# USBdrive_charging.net
KiCad netlist of a schematic drawn in Altium Designer
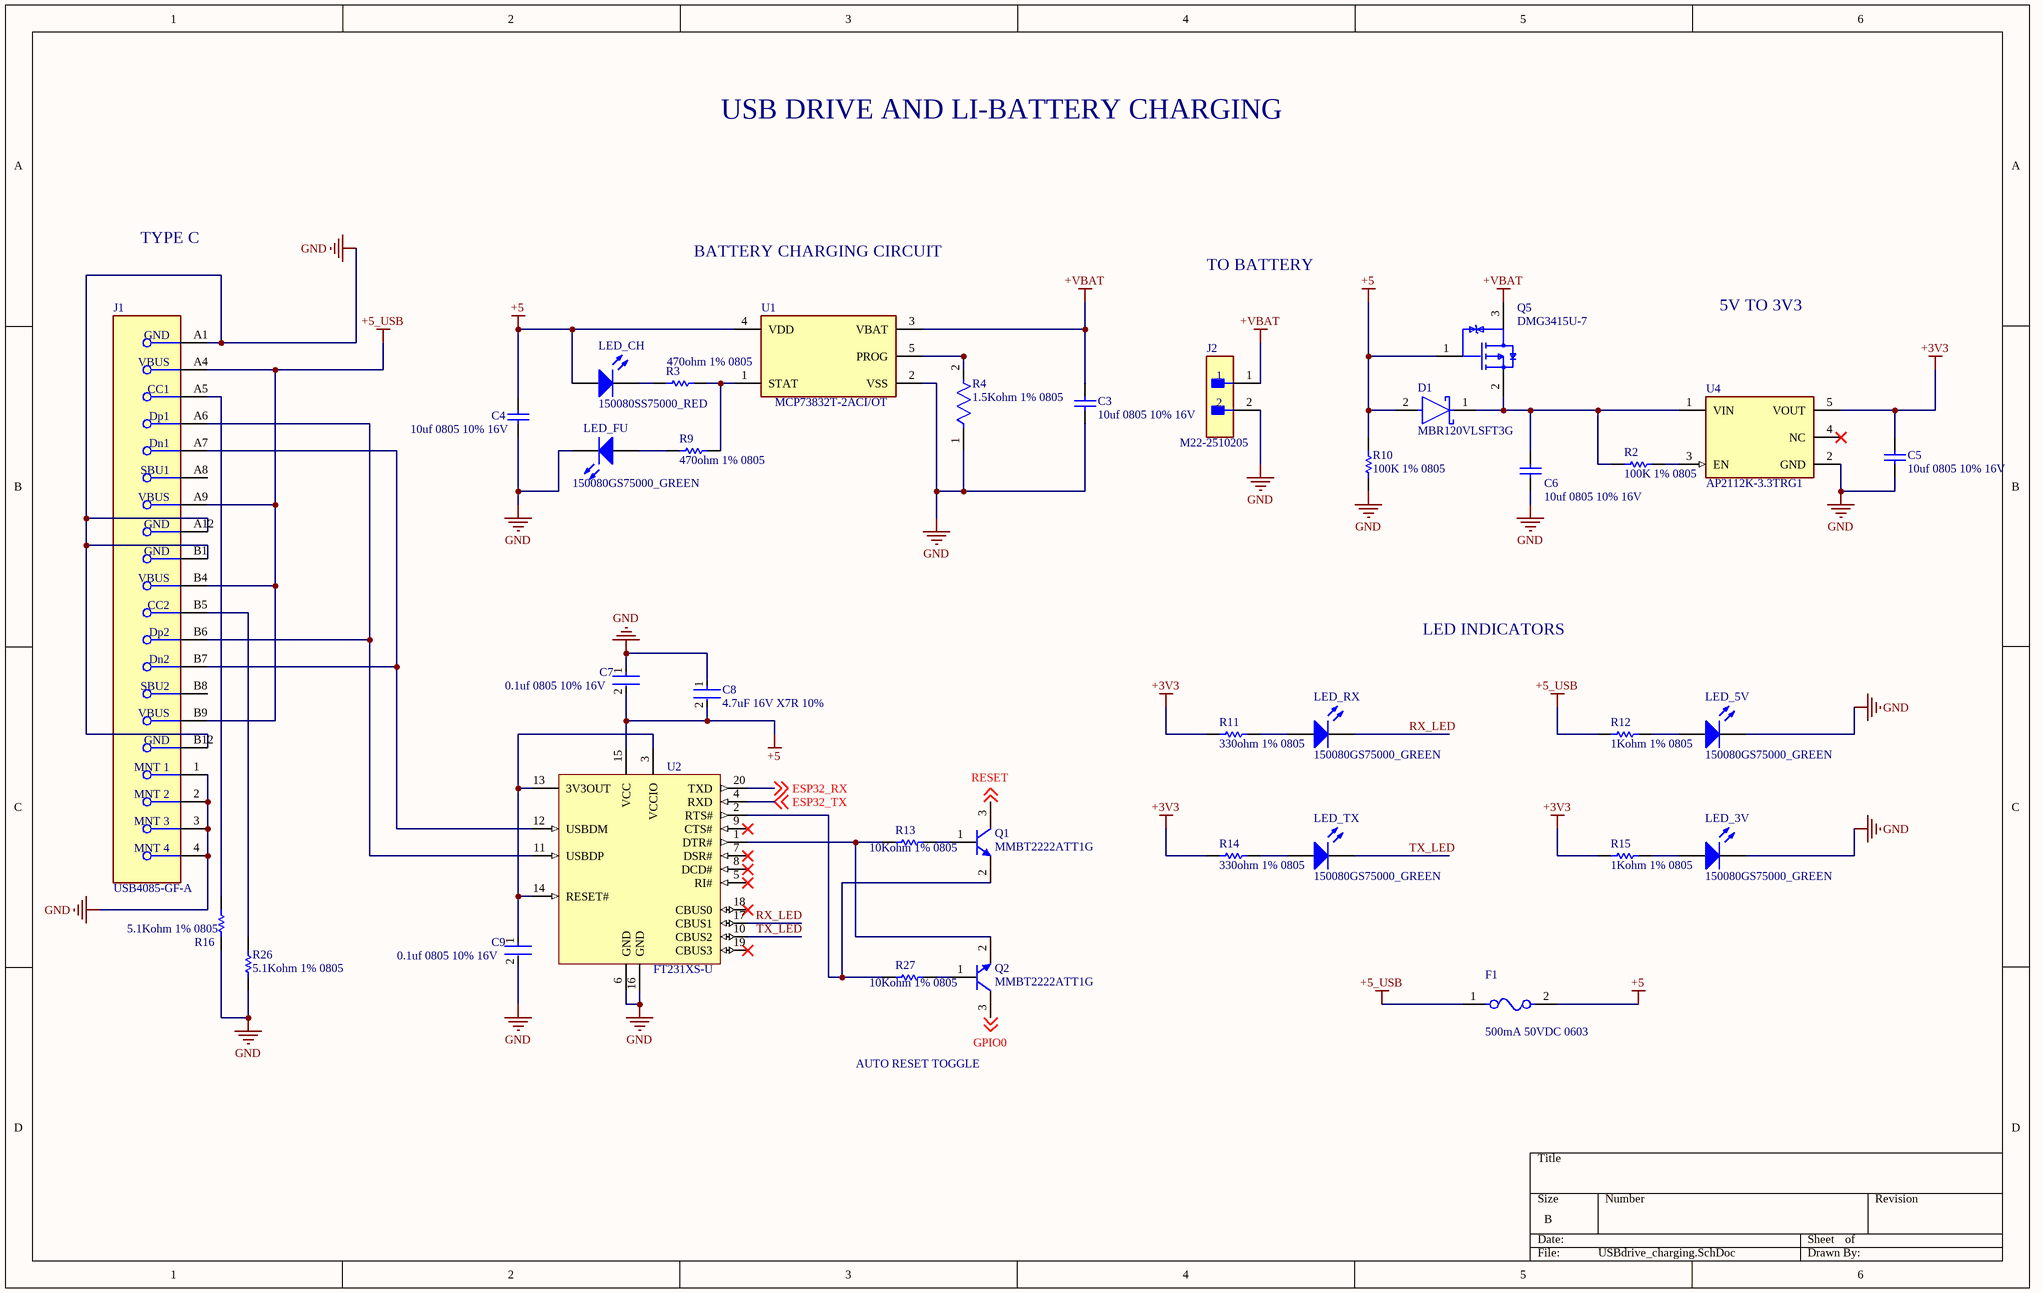
[diagram p0: USBdrive_charging.SchDoc]

(export (version "E")
  (design (tool "Eeschema 10.0.6"))
  (components
    (comp (ref "C3")
      (value "10uf 0805 10% 16V")
      (footprint "CAPC2013X140X50ML20T25")
      (fields
        (field (name "PART NUMBER") "0805YD106KAT2A")
        (field (name "MANUFACTURER") "AVX Interconnect / Elco")
      )
      (libsource (lib "Altium Content Vault") (part "CAP"))
    )
    (comp (ref "C4")
      (value "10uf 0805 10% 16V")
      (footprint "CAPC2013X140X50ML20T25")
      (fields
        (field (name "PART NUMBER") "0805YD106KAT2A")
        (field (name "MANUFACTURER") "AVX Interconnect / Elco")
      )
      (libsource (lib "Altium Content Vault") (part "CAP"))
    )
    (comp (ref "C5")
      (value "10uf 0805 10% 16V")
      (footprint "CAPC2013X140X50ML20T25")
      (fields
        (field (name "PART NUMBER") "0805YD106KAT2A")
        (field (name "MANUFACTURER") "AVX Interconnect / Elco")
      )
      (libsource (lib "Altium Content Vault") (part "CAP"))
    )
    (comp (ref "C6")
      (value "10uf 0805 10% 16V")
      (footprint "CAPC2013X140X50ML20T25")
      (fields
        (field (name "PART NUMBER") "0805YD106KAT2A")
        (field (name "MANUFACTURER") "AVX Interconnect / Elco")
      )
      (libsource (lib "Altium Content Vault") (part "CAP"))
    )
    (comp (ref "C7")
      (value "0.1uf 0805 10% 16V")
      (footprint "FP-CC0805-0_85-MFG")
      (description "CAP CER 0.1UF 16V X7R 0805")
      (fields
        (field (name "MANUFACTURER PART NUMBER") "CC0805KRX7R7BB104")
        (field (name "MANUFACTURER") "Yageo")
      )
      (libsource (lib "Altium Content Vault") (part "11868f565c42a9108669ba33697ecf6"))
    )
    (comp (ref "C8")
      (value "4.7uF 16V X7R 10%")
      (footprint "FP-CGA4J-IPC_A")
      (description "Cap Ceramic 4.7uF 16V X7R 10% Pad SMD 0805 +125°C Automotive T/R")
      (fields (field (name "TOLERANCE") "10%"))
      (libsource (lib "Altium Content Vault") (part "b4654b650e69147ec39a6b967a45e02"))
    )
    (comp (ref "C9")
      (value "0.1uf 0805 10% 16V")
      (footprint "FP-CC0805-0_85-MFG")
      (description "CAP CER 0.1UF 16V X7R 0805")
      (fields
        (field (name "MANUFACTURER PART NUMBER") "CC0805KRX7R7BB104")
        (field (name "MANUFACTURER") "Yageo")
      )
      (libsource (lib "Altium Content Vault") (part "11868f565c42a9108669ba33697ecf6"))
    )
    (comp (ref "D1")
      (value "MBR120VLSFT3G")
      (footprint "FP-498-MFG")
      (description "DIODE SCHOTTKY 20V 1A SOD123FL")
      (libsource (lib "Altium Content Vault") (part "1d6ec82d83fb6aee721767c19dac4b9"))
    )
    (comp (ref "F1")
      (value "500mA 50VDC 0603")
      (footprint "FP-SF-0603S-MFG")
      (description "FUSE BOARD MNT 500MA 50VDC 0603")
      (fields
        (field (name "MANUFACTURER") "Bourns Inc.")
        (field (name "MANUFACTURER PART NUMBER") "SF-0603S050-2")
      )
      (libsource (lib "Altium Content Vault") (part "5bcf9b9f640e542cf0359d10258e979"))
    )
    (comp (ref "J1")
      (value "USB4085-GF-A")
      (footprint "FP-USB4085-GF-A-MFG")
      (description "CONN RCPT USB2.0 TYPEC 16POS")
      (fields
        (field (name "MANUFACTURER") "Global Connector Technology")
        (field (name "OCTOPART") "https://octopart.com/usb4085-gf-a-global+connector+technology-94773699")
      )
      (libsource (lib "Altium Content Vault") (part "f6997dba88850a18107ac0013977506"))
    )
    (comp (ref "J2")
      (value "M22-2510205")
      (footprint "FP-M22-2510205-MFG")
      (description "CONN HEADER VERT 2POS 2MM")
      (fields
        (field (name "MANUFACTURER") "Harwin")
        (field (name "OCTOPART") "https://octopart.com/m22-2510205-harwin-2538221")
      )
      (libsource (lib "Altium Content Vault") (part "3bc925449376181038e59eaffc5286c"))
    )
    (comp (ref "LED_3V")
      (value "150080GS75000_GREEN")
      (footprint "0805_A")
      (description "SMD mono-color Chip LED, WL-SMCW, Green")
      (fields (field (name "PARTNUMBER") "150080GS75000") (field (name "MANUFACTURER") "Wuerth Elektronik"))
      (libsource (lib "Altium Content Vault") (part "WE-LED_K1A2-2"))
    )
    (comp (ref "LED_5V")
      (value "150080GS75000_GREEN")
      (footprint "0805_A")
      (description "SMD mono-color Chip LED, WL-SMCW, Green")
      (fields (field (name "PARTNUMBER") "150080GS75000") (field (name "MANUFACTURER") "Wuerth Elektronik"))
      (libsource (lib "Altium Content Vault") (part "WE-LED_K1A2-2"))
    )
    (comp (ref "LED_CH")
      (value "150080SS75000_RED")
      (footprint "0805_A")
      (description "SMD mono-color Chip LED, WL-SMCW, Super Red")
      (fields (field (name "MANUFACTURER") "Wuerth Elektronik") (field (name "PARTNUMBER") "150080SS75000"))
      (libsource (lib "Altium Content Vault") (part "WE-LED_K1A2-2"))
    )
    (comp (ref "LED_FU")
      (value "150080GS75000_GREEN")
      (footprint "0805_A")
      (description "SMD mono-color Chip LED, WL-SMCW, Green")
      (fields (field (name "PARTNUMBER") "150080GS75000") (field (name "MANUFACTURER") "Wuerth Elektronik"))
      (libsource (lib "Altium Content Vault") (part "WE-LED_K1A2-2"))
    )
    (comp (ref "LED_RX")
      (value "150080GS75000_GREEN")
      (footprint "0805_A")
      (description "SMD mono-color Chip LED, WL-SMCW, Green")
      (fields (field (name "PARTNUMBER") "150080GS75000") (field (name "MANUFACTURER") "Wuerth Elektronik"))
      (libsource (lib "Altium Content Vault") (part "WE-LED_K1A2-2"))
    )
    (comp (ref "LED_TX")
      (value "150080GS75000_GREEN")
      (footprint "0805_A")
      (description "SMD mono-color Chip LED, WL-SMCW, Green")
      (fields (field (name "PARTNUMBER") "150080GS75000") (field (name "MANUFACTURER") "Wuerth Elektronik"))
      (libsource (lib "Altium Content Vault") (part "WE-LED_K1A2-2"))
    )
    (comp (ref "Q1")
      (value "MMBT2222ATT1G")
      (footprint "ONSC-SC-75-3-463-01_V")
      (description "General Purpose Transistor, NPN Silicon, 3-Pin SC-75, Pb-Free, Tape and Reel")
      (fields (field (name "MANUFACTURER") "On Semiconductor"))
      (libsource (lib "Altium Content Vault") (part "ONSC-NPN-B1E2C3-3"))
    )
    (comp (ref "Q2")
      (value "MMBT2222ATT1G")
      (footprint "ONSC-SC-75-3-463-01_V")
      (description "General Purpose Transistor, NPN Silicon, 3-Pin SC-75, Pb-Free, Tape and Reel")
      (fields (field (name "MANUFACTURER") "On Semiconductor"))
      (libsource (lib "Altium Content Vault") (part "ONSC-NPN-B1E2C3-3"))
    )
    (comp (ref "Q5")
      (value "DMG3415U-7")
      (footprint "DMG3415U")
      (description "MOSFET P-CH 20V 4A SOT-23")
      (fields (field (name "MANUFACTURER") "Diodes"))
      (libsource (lib "Schlib1") (part "DMG3415U-7"))
    )
    (comp (ref "R2")
      (value "100K 1% 0805")
      (footprint "RESC2013X60X35ML10T20")
      (description "Chip Resistor, 100 KOhm, +/- 1%, 0.125 W, -55 to 155 degC, 0805 (2012 Metric), RoHS, Tape and Reel")
      (fields (field (name "MANUFACTURER") "Yageo") (field (name "TOLERANCE") "1%"))
      (libsource (lib "Altium Content Vault") (part "RES-2"))
    )
    (comp (ref "R3")
      (value "470ohm 1% 0805")
      (footprint "RESC2013X50X30LL20T20")
      (fields (field (name "MANUFACTURER") "Vishay Dale") (field (name "PART NUMBER") "CRCW0805470RFKEA"))
      (libsource (lib "Altium Content Vault") (part "RES"))
    )
    (comp (ref "R4")
      (value "1.5Kohm 1% 0805")
      (footprint "FP-RC2012-IPC_B")
      (description "Res Thick Film 0805 1.5kΩ 1% 0.125W ±100ppm/°C Molded SMD T/R")
      (fields (field (name "TOLERANCE") "1%"))
      (libsource (lib "Altium Content Vault") (part "1029c3af85768c4190bb7ad29bc67b5"))
    )
    (comp (ref "R9")
      (value "470ohm 1% 0805")
      (footprint "RESC2013X50X30LL20T20")
      (fields (field (name "MANUFACTURER") "Vishay Dale") (field (name "PART NUMBER") "CRCW0805470RFKEA"))
      (libsource (lib "Altium Content Vault") (part "RES"))
    )
    (comp (ref "R10")
      (value "100K 1% 0805")
      (footprint "RESC2013X60X35ML10T20")
      (description "Chip Resistor, 100 KOhm, +/- 1%, 0.125 W, -55 to 155 degC, 0805 (2012 Metric), RoHS, Tape and Reel")
      (fields (field (name "MANUFACTURER") "Yageo") (field (name "TOLERANCE") "1%"))
      (libsource (lib "Altium Content Vault") (part "RES-2"))
    )
    (comp (ref "R11")
      (value "330ohm 1% 0805")
      (footprint "RESC2013X70X40ML20T20")
      (fields (field (name "MANUFACTURER") "Panasonic") (field (name "PART NUMBER") "ERJ6ENF3300V"))
      (libsource (lib "Altium Content Vault") (part "RES"))
    )
    (comp (ref "R12")
      (value "1Kohm 1% 0805")
      (footprint "RESC2013X70X40ML20T20")
      (description "Chip Resistor, 1 KOhm, +/- 1%, 0.125 W, -55 to 155 degC, 0805 (2012 Metric), RoHS, Tape and Reel")
      (fields (field (name "MANUFACTURER") "Panasonic"))
      (libsource (lib "Altium Content Vault") (part "RES-2"))
    )
    (comp (ref "R13")
      (value "10Kohm 1% 0805")
      (footprint "RESC2013X60X35NL10T20")
      (description "Chip Resistor, 10 KOhm, +/- 1%, 0.125 W, -55 to 155 degC, 0805 (2012 Metric), RoHS, Tape and Reel")
      (fields (field (name "MANUFACTURER") "Yageo"))
      (libsource (lib "Altium Content Vault") (part "RES-2"))
    )
    (comp (ref "R14")
      (value "330ohm 1% 0805")
      (footprint "RESC2013X70X40ML20T20")
      (fields (field (name "MANUFACTURER") "Panasonic") (field (name "PART NUMBER") "ERJ6ENF3300V"))
      (libsource (lib "Altium Content Vault") (part "RES"))
    )
    (comp (ref "R15")
      (value "1Kohm 1% 0805")
      (footprint "RESC2013X70X40ML20T20")
      (description "Chip Resistor, 1 KOhm, +/- 1%, 0.125 W, -55 to 155 degC, 0805 (2012 Metric), RoHS, Tape and Reel")
      (fields (field (name "MANUFACTURER") "Panasonic"))
      (libsource (lib "Altium Content Vault") (part "RES-2"))
    )
    (comp (ref "R16")
      (value "5.1Kohm 1% 0805")
      (footprint "RESC2013X50X30LL20T20")
      (fields (field (name "MANUFACTURER") "Vishay Dale") (field (name "PART NUMBER") "CRCW0805470RFKEA"))
      (libsource (lib "Altium Content Vault") (part "RES"))
    )
    (comp (ref "R26")
      (value "5.1Kohm 1% 0805")
      (footprint "RESC2013X70X40ML20T20")
      (fields (field (name "PART NUMBER") "ERJ6ENF5101V") (field (name "MANUFACTURER") "Panasonic"))
      (libsource (lib "Altium Content Vault") (part "RES"))
    )
    (comp (ref "R27")
      (value "10Kohm 1% 0805")
      (footprint "RESC2013X60X35NL10T20")
      (description "Chip Resistor, 10 KOhm, +/- 1%, 0.125 W, -55 to 155 degC, 0805 (2012 Metric), RoHS, Tape and Reel")
      (fields (field (name "MANUFACTURER") "Yageo"))
      (libsource (lib "Altium Content Vault") (part "RES-2"))
    )
    (comp (ref "U1")
      (value "MCP73832T-2ACI/OT")
      (footprint "FP-C04-091-OT-MFG")
      (description "IC LI-ION/LI-POLY CTRLR SOT23-5")
      (libsource (lib "Altium Content Vault") (part "61f5a3bb3429d9e0caadea342aa3b19"))
    )
    (comp (ref "U2")
      (value "FT231XS-U")
      (footprint "SSOP-20_L")
      (fields (field (name "MANUFACTURER") "FTDI"))
      (libsource (lib "Altium Content Vault") (part "COM-USB-FT231XS-IL20"))
    )
    (comp (ref "U4")
      (value "AP2112K-3.3TRG1")
      (footprint "FP-SOT25-IPC_A")
      (description "IC REG LINEAR 3.3V 600MA SOT25")
      (libsource (lib "Altium Content Vault") (part "c8ab751aee5229183125ab046a11caa"))
    )
  )
  (nets
    (net (code "1") (name "+3V3") (class "Default")
      (node (ref "C5") (pin "2") (pinfunction "2_2") (pintype "passive"))
      (node (ref "R11") (pin "1") (pinfunction "1_1") (pintype "passive"))
      (node (ref "R14") (pin "1") (pinfunction "1_1") (pintype "passive"))
      (node (ref "R15") (pin "1") (pinfunction "1_1") (pintype "passive"))
      (node (ref "U4") (pin "5") (pinfunction "VOUT_5") (pintype "power_in"))
    )
    (net (code "2") (name "+5") (class "Default")
      (node (ref "C4") (pin "2") (pinfunction "2_2") (pintype "passive"))
      (node (ref "C7") (pin "2") (pinfunction "2_2") (pintype "passive"))
      (node (ref "C8") (pin "2") (pinfunction "2_2") (pintype "passive"))
      (node (ref "D1") (pin "2") (pinfunction "A_2") (pintype "passive"))
      (node (ref "F1") (pin "2") (pinfunction "2_2") (pintype "passive"))
      (node (ref "LED_CH") (pin "2") (pinfunction "A_2") (pintype "passive"))
      (node (ref "Q5") (pin "1") (pinfunction "G_1") (pintype "passive"))
      (node (ref "R10") (pin "2") (pinfunction "2_2") (pintype "passive"))
      (node (ref "U1") (pin "4") (pinfunction "VDD_4") (pintype "power_in"))
      (node (ref "U2") (pin "15") (pinfunction "VCC_15") (pintype "power_in"))
    )
    (net (code "3") (name "+5_USB") (class "Default")
      (node (ref "F1") (pin "1") (pinfunction "1_1") (pintype "passive"))
      (node (ref "J1") (pin "A4") (pinfunction "VBUS_A4") (pintype "power_in"))
      (node (ref "J1") (pin "A9") (pinfunction "VBUS_A9") (pintype "power_in"))
      (node (ref "J1") (pin "B4") (pinfunction "VBUS_B4") (pintype "power_in"))
      (node (ref "J1") (pin "B9") (pinfunction "VBUS_B9") (pintype "power_in"))
      (node (ref "R12") (pin "1") (pinfunction "1_1") (pintype "passive"))
    )
    (net (code "4") (name "+VBAT") (class "Default")
      (node (ref "C3") (pin "2") (pinfunction "2_2") (pintype "passive"))
      (node (ref "J2") (pin "1") (pinfunction "1_1") (pintype "passive"))
      (node (ref "Q5") (pin "3") (pinfunction "D_3") (pintype "passive"))
      (node (ref "U1") (pin "3") (pinfunction "VBAT_3") (pintype "power_in"))
    )
    (net (code "5") (name "/RX_LED") (class "Default")
      (node (ref "LED_RX") (pin "1") (pinfunction "K_1") (pintype "passive"))
      (node (ref "U2") (pin "17") (pinfunction "CBUS1_17") (pintype "bidirectional"))
    )
    (net (code "6") (name "/TX_LED") (class "Default")
      (node (ref "LED_TX") (pin "1") (pinfunction "K_1") (pintype "passive"))
      (node (ref "U2") (pin "10") (pinfunction "CBUS2_10") (pintype "bidirectional"))
    )
    (net (code "7") (name "ESP32_RX") (class "Default")
      (node (ref "U2") (pin "20") (pinfunction "TXD_20") (pintype "output"))
    )
    (net (code "8") (name "ESP32_TX") (class "Default")
      (node (ref "U2") (pin "4") (pinfunction "RXD_4") (pintype "input"))
    )
    (net (code "9") (name "GND") (class "Default")
      (node (ref "C3") (pin "1") (pinfunction "1_1") (pintype "passive"))
      (node (ref "C4") (pin "1") (pinfunction "1_1") (pintype "passive"))
      (node (ref "C5") (pin "1") (pinfunction "1_1") (pintype "passive"))
      (node (ref "C6") (pin "1") (pinfunction "1_1") (pintype "passive"))
      (node (ref "C7") (pin "1") (pinfunction "1_1") (pintype "passive"))
      (node (ref "C8") (pin "1") (pinfunction "1_1") (pintype "passive"))
      (node (ref "C9") (pin "2") (pinfunction "2_2") (pintype "passive"))
      (node (ref "J1") (pin "1") (pinfunction "MNT_1_1") (pintype "passive"))
      (node (ref "J1") (pin "2") (pinfunction "MNT_2_2") (pintype "passive"))
      (node (ref "J1") (pin "3") (pinfunction "MNT_3_3") (pintype "passive"))
      (node (ref "J1") (pin "4") (pinfunction "MNT_4_4") (pintype "passive"))
      (node (ref "J1") (pin "A1") (pinfunction "GND_A1") (pintype "power_in"))
      (node (ref "J1") (pin "A12") (pinfunction "GND_A12") (pintype "power_in"))
      (node (ref "J1") (pin "B1") (pinfunction "GND_B1") (pintype "power_in"))
      (node (ref "J1") (pin "B12") (pinfunction "GND_B12") (pintype "power_in"))
      (node (ref "J2") (pin "2") (pinfunction "2_2") (pintype "passive"))
      (node (ref "LED_3V") (pin "1") (pinfunction "K_1") (pintype "passive"))
      (node (ref "LED_5V") (pin "1") (pinfunction "K_1") (pintype "passive"))
      (node (ref "LED_FU") (pin "1") (pinfunction "K_1") (pintype "passive"))
      (node (ref "R10") (pin "1") (pinfunction "1_1") (pintype "passive"))
      (node (ref "R16") (pin "1") (pinfunction "1_1") (pintype "passive"))
      (node (ref "R26") (pin "1") (pinfunction "1_1") (pintype "passive"))
      (node (ref "R4") (pin "1") (pinfunction "1_1") (pintype "passive"))
      (node (ref "U1") (pin "2") (pinfunction "VSS_2") (pintype "power_in"))
      (node (ref "U2") (pin "16") (pinfunction "GND_16") (pintype "power_in"))
      (node (ref "U2") (pin "6") (pinfunction "GND_6") (pintype "power_in"))
      (node (ref "U4") (pin "2") (pinfunction "GND_2") (pintype "power_in"))
    )
    (net (code "10") (name "GPIO0") (class "Default")
      (node (ref "Q2") (pin "3") (pinfunction "C_3") (pintype "passive"))
    )
    (net (code "11") (name "Net-(D1-C)") (class "Default")
      (node (ref "C6") (pin "2") (pinfunction "2_2") (pintype "passive"))
      (node (ref "D1") (pin "1") (pinfunction "C_1") (pintype "passive"))
      (node (ref "Q5") (pin "2") (pinfunction "S_2") (pintype "passive"))
      (node (ref "R2") (pin "2") (pinfunction "2_2") (pintype "passive"))
      (node (ref "U4") (pin "1") (pinfunction "VIN_1") (pintype "power_in"))
    )
    (net (code "12") (name "Net-(J1-CC1)") (class "Default")
      (node (ref "J1") (pin "A5") (pinfunction "CC1_A5") (pintype "passive"))
      (node (ref "R16") (pin "2") (pinfunction "2_2") (pintype "passive"))
    )
    (net (code "13") (name "Net-(J1-CC2)") (class "Default")
      (node (ref "J1") (pin "B5") (pinfunction "CC2_B5") (pintype "passive"))
      (node (ref "R26") (pin "2") (pinfunction "2_2") (pintype "passive"))
    )
    (net (code "14") (name "Net-(J1-Dn1)") (class "Default")
      (node (ref "J1") (pin "A7") (pinfunction "Dn1_A7") (pintype "passive"))
      (node (ref "J1") (pin "B7") (pinfunction "Dn2_B7") (pintype "passive"))
      (node (ref "U2") (pin "12") (pinfunction "USBDM_12") (pintype "input"))
    )
    (net (code "15") (name "Net-(J1-Dp1)") (class "Default")
      (node (ref "J1") (pin "A6") (pinfunction "Dp1_A6") (pintype "passive"))
      (node (ref "J1") (pin "B6") (pinfunction "Dp2_B6") (pintype "passive"))
      (node (ref "U2") (pin "11") (pinfunction "USBDP_11") (pintype "input"))
    )
    (net (code "16") (name "Net-(LED_3V-A)") (class "Default")
      (node (ref "LED_3V") (pin "2") (pinfunction "A_2") (pintype "passive"))
      (node (ref "R15") (pin "2") (pinfunction "2_2") (pintype "passive"))
    )
    (net (code "17") (name "Net-(LED_5V-A)") (class "Default")
      (node (ref "LED_5V") (pin "2") (pinfunction "A_2") (pintype "passive"))
      (node (ref "R12") (pin "2") (pinfunction "2_2") (pintype "passive"))
    )
    (net (code "18") (name "Net-(LED_CH-K)") (class "Default")
      (node (ref "LED_CH") (pin "1") (pinfunction "K_1") (pintype "passive"))
      (node (ref "R3") (pin "1") (pinfunction "1_1") (pintype "passive"))
    )
    (net (code "19") (name "Net-(LED_FU-A)") (class "Default")
      (node (ref "LED_FU") (pin "2") (pinfunction "A_2") (pintype "passive"))
      (node (ref "R9") (pin "1") (pinfunction "1_1") (pintype "passive"))
    )
    (net (code "20") (name "Net-(LED_RX-A)") (class "Default")
      (node (ref "LED_RX") (pin "2") (pinfunction "A_2") (pintype "passive"))
      (node (ref "R11") (pin "2") (pinfunction "2_2") (pintype "passive"))
    )
    (net (code "21") (name "Net-(LED_TX-A)") (class "Default")
      (node (ref "LED_TX") (pin "2") (pinfunction "A_2") (pintype "passive"))
      (node (ref "R14") (pin "2") (pinfunction "2_2") (pintype "passive"))
    )
    (net (code "22") (name "Net-(Q1-B)") (class "Default")
      (node (ref "Q1") (pin "1") (pinfunction "B_1") (pintype "passive"))
      (node (ref "R13") (pin "2") (pinfunction "2_2") (pintype "passive"))
    )
    (net (code "23") (name "Net-(Q1-E)") (class "Default")
      (node (ref "Q1") (pin "2") (pinfunction "E_2") (pintype "passive"))
      (node (ref "R27") (pin "1") (pinfunction "1_1") (pintype "passive"))
      (node (ref "U2") (pin "2") (pinfunction "RTS#_2") (pintype "output"))
    )
    (net (code "24") (name "Net-(Q2-B)") (class "Default")
      (node (ref "Q2") (pin "1") (pinfunction "B_1") (pintype "passive"))
      (node (ref "R27") (pin "2") (pinfunction "2_2") (pintype "passive"))
    )
    (net (code "25") (name "Net-(Q2-E)") (class "Default")
      (node (ref "Q2") (pin "2") (pinfunction "E_2") (pintype "passive"))
      (node (ref "R13") (pin "1") (pinfunction "1_1") (pintype "passive"))
      (node (ref "U2") (pin "1") (pinfunction "DTR#_1") (pintype "output"))
    )
    (net (code "26") (name "Net-(U1-PROG)") (class "Default")
      (node (ref "R4") (pin "2") (pinfunction "2_2") (pintype "passive"))
      (node (ref "U1") (pin "5") (pinfunction "PROG_5") (pintype "passive"))
    )
    (net (code "27") (name "Net-(U1-STAT)") (class "Default")
      (node (ref "R3") (pin "2") (pinfunction "2_2") (pintype "passive"))
      (node (ref "R9") (pin "2") (pinfunction "2_2") (pintype "passive"))
      (node (ref "U1") (pin "1") (pinfunction "STAT_1") (pintype "passive"))
    )
    (net (code "28") (name "Net-(U2-3V3OUT)") (class "Default")
      (node (ref "C9") (pin "1") (pinfunction "1_1") (pintype "passive"))
      (node (ref "U2") (pin "13") (pinfunction "3V3OUT_13") (pintype "power_in"))
      (node (ref "U2") (pin "14") (pinfunction "RESET#_14") (pintype "input"))
      (node (ref "U2") (pin "3") (pinfunction "VCCIO_3") (pintype "power_in"))
    )
    (net (code "29") (name "Net-(U4-EN)") (class "Default")
      (node (ref "R2") (pin "1") (pinfunction "1_1") (pintype "passive"))
      (node (ref "U4") (pin "3") (pinfunction "EN_3") (pintype "input"))
    )
    (net (code "30") (name "RESET") (class "Default")
      (node (ref "Q1") (pin "3") (pinfunction "C_3") (pintype "passive"))
    )
    (net (code "31") (name "unconnected-(J1-SBU1-PadA8)") (class "Default")
      (node (ref "J1") (pin "A8") (pinfunction "SBU1_A8") (pintype "passive"))
    )
    (net (code "32") (name "unconnected-(J1-SBU2-PadB8)") (class "Default")
      (node (ref "J1") (pin "B8") (pinfunction "SBU2_B8") (pintype "passive"))
    )
    (net (code "33") (name "unconnected-(U2-CBUS0-Pad18)") (class "Default")
      (node (ref "U2") (pin "18") (pinfunction "CBUS0_18") (pintype "bidirectional+no_connect"))
    )
    (net (code "34") (name "unconnected-(U2-CBUS3-Pad19)") (class "Default")
      (node (ref "U2") (pin "19") (pinfunction "CBUS3_19") (pintype "bidirectional+no_connect"))
    )
    (net (code "35") (name "unconnected-(U2-CTS#-Pad9)") (class "Default")
      (node (ref "U2") (pin "9") (pinfunction "CTS#_9") (pintype "input+no_connect"))
    )
    (net (code "36") (name "unconnected-(U2-DCD#-Pad8)") (class "Default")
      (node (ref "U2") (pin "8") (pinfunction "DCD#_8") (pintype "input+no_connect"))
    )
    (net (code "37") (name "unconnected-(U2-DSR#-Pad7)") (class "Default")
      (node (ref "U2") (pin "7") (pinfunction "DSR#_7") (pintype "input+no_connect"))
    )
    (net (code "38") (name "unconnected-(U2-RI#-Pad5)") (class "Default")
      (node (ref "U2") (pin "5") (pinfunction "RI#_5") (pintype "input+no_connect"))
    )
    (net (code "39") (name "unconnected-(U4-NC-Pad4)") (class "Default")
      (node (ref "U4") (pin "4") (pinfunction "NC_4") (pintype "passive+no_connect"))
    )
  )
)
